# buckpuckV5_2014-12-10.net
KiCad netlist of a schematic drawn in EAGLE
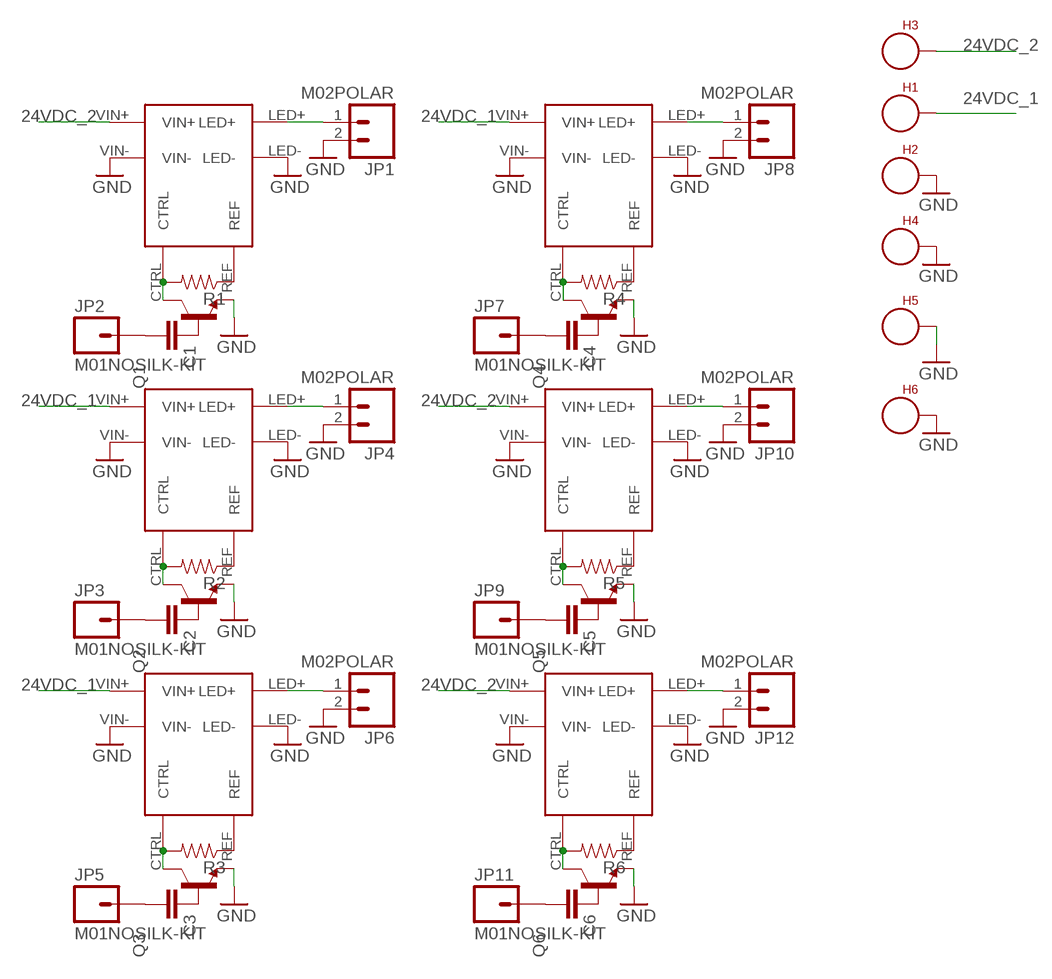
[diagram p0: schematic, sheet 1]

(export (version "E")
  (design (tool "Eeschema 10.0.6"))
  (components
    (comp (ref "C1")
      (value "CAPEZ")
      (footprint "eagle-import:CAP-PTH-SMALLEZ")
      (libsource (lib "eagle-import") (part "CAPEZ"))
    )
    (comp (ref "C2")
      (value "CAPEZ")
      (footprint "eagle-import:CAP-PTH-SMALLEZ")
      (libsource (lib "eagle-import") (part "CAPEZ"))
    )
    (comp (ref "C3")
      (value "CAPEZ")
      (footprint "eagle-import:CAP-PTH-SMALLEZ")
      (libsource (lib "eagle-import") (part "CAPEZ"))
    )
    (comp (ref "C4")
      (value "CAPEZ")
      (footprint "eagle-import:CAP-PTH-SMALLEZ")
      (libsource (lib "eagle-import") (part "CAPEZ"))
    )
    (comp (ref "C5")
      (value "CAPEZ")
      (footprint "eagle-import:CAP-PTH-SMALLEZ")
      (libsource (lib "eagle-import") (part "CAPEZ"))
    )
    (comp (ref "C6")
      (value "CAPEZ")
      (footprint "eagle-import:CAP-PTH-SMALLEZ")
      (libsource (lib "eagle-import") (part "CAPEZ"))
    )
    (comp (ref "H1")
      (value "SEW_HOLE")
      (footprint "eagle-import:SIMPLE_HOLE")
      (libsource (lib "eagle-import") (part "SEW_HOLE"))
    )
    (comp (ref "H2")
      (value "SEW_HOLE")
      (footprint "eagle-import:SIMPLE_HOLE")
      (libsource (lib "eagle-import") (part "SEW_HOLE"))
    )
    (comp (ref "H3")
      (value "SEW_HOLE")
      (footprint "eagle-import:SIMPLE_HOLE")
      (libsource (lib "eagle-import") (part "SEW_HOLE"))
    )
    (comp (ref "H4")
      (value "SEW_HOLE")
      (footprint "eagle-import:SIMPLE_HOLE")
      (libsource (lib "eagle-import") (part "SEW_HOLE"))
    )
    (comp (ref "H5")
      (value "SEW_HOLE")
      (footprint "eagle-import:SIMPLE_HOLE")
      (libsource (lib "eagle-import") (part "SEW_HOLE"))
    )
    (comp (ref "H6")
      (value "SEW_HOLE")
      (footprint "eagle-import:SIMPLE_HOLE")
      (libsource (lib "eagle-import") (part "SEW_HOLE"))
    )
    (comp (ref "JP1")
      (value "M02POLAR")
      (footprint "eagle-import:MOLEX-1X2")
      (libsource (lib "eagle-import") (part "M02POLAR"))
    )
    (comp (ref "JP2")
      (value "M01NOSILK-KIT")
      (footprint "eagle-import:1X01NS-KIT")
      (libsource (lib "eagle-import") (part "M01NOSILK-KIT"))
    )
    (comp (ref "JP3")
      (value "M01NOSILK-KIT")
      (footprint "eagle-import:1X01NS-KIT")
      (libsource (lib "eagle-import") (part "M01NOSILK-KIT"))
    )
    (comp (ref "JP4")
      (value "M02POLAR")
      (footprint "eagle-import:MOLEX-1X2")
      (libsource (lib "eagle-import") (part "M02POLAR"))
    )
    (comp (ref "JP5")
      (value "M01NOSILK-KIT")
      (footprint "eagle-import:1X01NS-KIT")
      (libsource (lib "eagle-import") (part "M01NOSILK-KIT"))
    )
    (comp (ref "JP6")
      (value "M02POLAR")
      (footprint "eagle-import:MOLEX-1X2")
      (libsource (lib "eagle-import") (part "M02POLAR"))
    )
    (comp (ref "JP7")
      (value "M01NOSILK-KIT")
      (footprint "eagle-import:1X01NS-KIT")
      (libsource (lib "eagle-import") (part "M01NOSILK-KIT"))
    )
    (comp (ref "JP8")
      (value "M02POLAR")
      (footprint "eagle-import:MOLEX-1X2")
      (libsource (lib "eagle-import") (part "M02POLAR"))
    )
    (comp (ref "JP9")
      (value "M01NOSILK-KIT")
      (footprint "eagle-import:1X01NS-KIT")
      (libsource (lib "eagle-import") (part "M01NOSILK-KIT"))
    )
    (comp (ref "JP10")
      (value "M02POLAR")
      (footprint "eagle-import:MOLEX-1X2")
      (libsource (lib "eagle-import") (part "M02POLAR"))
    )
    (comp (ref "JP11")
      (value "M01NOSILK-KIT")
      (footprint "eagle-import:1X01NS-KIT")
      (libsource (lib "eagle-import") (part "M01NOSILK-KIT"))
    )
    (comp (ref "JP12")
      (value "M02POLAR")
      (footprint "eagle-import:MOLEX-1X2")
      (libsource (lib "eagle-import") (part "M02POLAR"))
    )
    (comp (ref "Q1")
      (value "TRANSISTOR_BJT_NPN-TO-92-EBC")
      (footprint "eagle-import:TO-92")
      (libsource (lib "eagle-import") (part "TRANSISTOR_BJT_NPN-TO-92-EBC"))
    )
    (comp (ref "Q2")
      (value "TRANSISTOR_BJT_NPN-TO-92-EBC")
      (footprint "eagle-import:TO-92")
      (libsource (lib "eagle-import") (part "TRANSISTOR_BJT_NPN-TO-92-EBC"))
    )
    (comp (ref "Q3")
      (value "TRANSISTOR_BJT_NPN-TO-92-EBC")
      (footprint "eagle-import:TO-92")
      (libsource (lib "eagle-import") (part "TRANSISTOR_BJT_NPN-TO-92-EBC"))
    )
    (comp (ref "Q4")
      (value "TRANSISTOR_BJT_NPN-TO-92-EBC")
      (footprint "eagle-import:TO-92")
      (libsource (lib "eagle-import") (part "TRANSISTOR_BJT_NPN-TO-92-EBC"))
    )
    (comp (ref "Q5")
      (value "TRANSISTOR_BJT_NPN-TO-92-EBC")
      (footprint "eagle-import:TO-92")
      (libsource (lib "eagle-import") (part "TRANSISTOR_BJT_NPN-TO-92-EBC"))
    )
    (comp (ref "Q6")
      (value "TRANSISTOR_BJT_NPN-TO-92-EBC")
      (footprint "eagle-import:TO-92")
      (libsource (lib "eagle-import") (part "TRANSISTOR_BJT_NPN-TO-92-EBC"))
    )
    (comp (ref "R1")
      (value "RESISTOREZ")
      (footprint "eagle-import:AXIAL-0.3EZ")
      (libsource (lib "eagle-import") (part "RESISTOREZ"))
    )
    (comp (ref "R2")
      (value "RESISTOREZ")
      (footprint "eagle-import:AXIAL-0.3EZ")
      (libsource (lib "eagle-import") (part "RESISTOREZ"))
    )
    (comp (ref "R3")
      (value "RESISTOREZ")
      (footprint "eagle-import:AXIAL-0.3EZ")
      (libsource (lib "eagle-import") (part "RESISTOREZ"))
    )
    (comp (ref "R4")
      (value "RESISTOREZ")
      (footprint "eagle-import:AXIAL-0.3EZ")
      (libsource (lib "eagle-import") (part "RESISTOREZ"))
    )
    (comp (ref "R5")
      (value "RESISTOREZ")
      (footprint "eagle-import:AXIAL-0.3EZ")
      (libsource (lib "eagle-import") (part "RESISTOREZ"))
    )
    (comp (ref "R6")
      (value "RESISTOREZ")
      (footprint "eagle-import:AXIAL-0.3EZ")
      (libsource (lib "eagle-import") (part "RESISTOREZ"))
    )
    (comp (ref "U$1")
      (value "BUCKPUCK")
      (footprint "eagle-import:BUCKPUCK")
      (libsource (lib "eagle-import") (part "BUCKPUCK"))
    )
    (comp (ref "U$2")
      (value "BUCKPUCK")
      (footprint "eagle-import:BUCKPUCK")
      (libsource (lib "eagle-import") (part "BUCKPUCK"))
    )
    (comp (ref "U$3")
      (value "BUCKPUCK")
      (footprint "eagle-import:BUCKPUCK")
      (libsource (lib "eagle-import") (part "BUCKPUCK"))
    )
    (comp (ref "U$4")
      (value "BUCKPUCK")
      (footprint "eagle-import:BUCKPUCK")
      (libsource (lib "eagle-import") (part "BUCKPUCK"))
    )
    (comp (ref "U$5")
      (value "BUCKPUCK")
      (footprint "eagle-import:BUCKPUCK")
      (libsource (lib "eagle-import") (part "BUCKPUCK"))
    )
    (comp (ref "U$6")
      (value "BUCKPUCK")
      (footprint "eagle-import:BUCKPUCK")
      (libsource (lib "eagle-import") (part "BUCKPUCK"))
    )
  )
  (nets
    (net (code "1") (name "/24VDC_1") (class "Default")
      (node (ref "H1") (pin "P$1") (pinfunction "P$1_P$1") (pintype "bidirectional"))
      (node (ref "U$2") (pin "VIN+") (pinfunction "VIN+_VIN+") (pintype "bidirectional"))
      (node (ref "U$3") (pin "VIN+") (pinfunction "VIN+_VIN+") (pintype "bidirectional"))
      (node (ref "U$4") (pin "VIN+") (pinfunction "VIN+_VIN+") (pintype "bidirectional"))
    )
    (net (code "2") (name "/24VDC_2") (class "Default")
      (node (ref "H3") (pin "P$1") (pinfunction "P$1_P$1") (pintype "bidirectional"))
      (node (ref "U$1") (pin "VIN+") (pinfunction "VIN+_VIN+") (pintype "bidirectional"))
      (node (ref "U$5") (pin "VIN+") (pinfunction "VIN+_VIN+") (pintype "bidirectional"))
      (node (ref "U$6") (pin "VIN+") (pinfunction "VIN+_VIN+") (pintype "bidirectional"))
    )
    (net (code "3") (name "GND") (class "Default")
      (node (ref "H2") (pin "P$1") (pinfunction "P$1_P$1") (pintype "bidirectional"))
      (node (ref "H4") (pin "P$1") (pinfunction "P$1_P$1") (pintype "bidirectional"))
      (node (ref "H5") (pin "P$1") (pinfunction "P$1_P$1") (pintype "bidirectional"))
      (node (ref "H6") (pin "P$1") (pinfunction "P$1_P$1") (pintype "bidirectional"))
      (node (ref "JP1") (pin "2") (pinfunction "2_2") (pintype "passive"))
      (node (ref "JP10") (pin "2") (pinfunction "2_2") (pintype "passive"))
      (node (ref "JP12") (pin "2") (pinfunction "2_2") (pintype "passive"))
      (node (ref "JP4") (pin "2") (pinfunction "2_2") (pintype "passive"))
      (node (ref "JP6") (pin "2") (pinfunction "2_2") (pintype "passive"))
      (node (ref "JP8") (pin "2") (pinfunction "2_2") (pintype "passive"))
      (node (ref "Q1") (pin "1") (pinfunction "E_1") (pintype "passive"))
      (node (ref "Q2") (pin "1") (pinfunction "E_1") (pintype "passive"))
      (node (ref "Q3") (pin "1") (pinfunction "E_1") (pintype "passive"))
      (node (ref "Q4") (pin "1") (pinfunction "E_1") (pintype "passive"))
      (node (ref "Q5") (pin "1") (pinfunction "E_1") (pintype "passive"))
      (node (ref "Q6") (pin "1") (pinfunction "E_1") (pintype "passive"))
      (node (ref "U$1") (pin "LED-") (pinfunction "LED-_LED-") (pintype "bidirectional"))
      (node (ref "U$1") (pin "VIN-") (pinfunction "VIN-_VIN-") (pintype "bidirectional"))
      (node (ref "U$2") (pin "LED-") (pinfunction "LED-_LED-") (pintype "bidirectional"))
      (node (ref "U$2") (pin "VIN-") (pinfunction "VIN-_VIN-") (pintype "bidirectional"))
      (node (ref "U$3") (pin "LED-") (pinfunction "LED-_LED-") (pintype "bidirectional"))
      (node (ref "U$3") (pin "VIN-") (pinfunction "VIN-_VIN-") (pintype "bidirectional"))
      (node (ref "U$4") (pin "LED-") (pinfunction "LED-_LED-") (pintype "bidirectional"))
      (node (ref "U$4") (pin "VIN-") (pinfunction "VIN-_VIN-") (pintype "bidirectional"))
      (node (ref "U$5") (pin "LED-") (pinfunction "LED-_LED-") (pintype "bidirectional"))
      (node (ref "U$5") (pin "VIN-") (pinfunction "VIN-_VIN-") (pintype "bidirectional"))
      (node (ref "U$6") (pin "LED-") (pinfunction "LED-_LED-") (pintype "bidirectional"))
      (node (ref "U$6") (pin "VIN-") (pinfunction "VIN-_VIN-") (pintype "bidirectional"))
    )
    (net (code "4") (name "Net-(C1-Pad2)") (class "Default")
      (node (ref "C1") (pin "2") (pinfunction "2_2") (pintype "passive"))
      (node (ref "JP2") (pin "1") (pinfunction "1_1") (pintype "passive"))
    )
    (net (code "5") (name "Net-(C2-Pad2)") (class "Default")
      (node (ref "C2") (pin "2") (pinfunction "2_2") (pintype "passive"))
      (node (ref "JP3") (pin "1") (pinfunction "1_1") (pintype "passive"))
    )
    (net (code "6") (name "Net-(C3-Pad2)") (class "Default")
      (node (ref "C3") (pin "2") (pinfunction "2_2") (pintype "passive"))
      (node (ref "JP5") (pin "1") (pinfunction "1_1") (pintype "passive"))
    )
    (net (code "7") (name "Net-(C4-Pad2)") (class "Default")
      (node (ref "C4") (pin "2") (pinfunction "2_2") (pintype "passive"))
      (node (ref "JP7") (pin "1") (pinfunction "1_1") (pintype "passive"))
    )
    (net (code "8") (name "Net-(C5-Pad2)") (class "Default")
      (node (ref "C5") (pin "2") (pinfunction "2_2") (pintype "passive"))
      (node (ref "JP9") (pin "1") (pinfunction "1_1") (pintype "passive"))
    )
    (net (code "9") (name "Net-(C6-Pad2)") (class "Default")
      (node (ref "C6") (pin "2") (pinfunction "2_2") (pintype "passive"))
      (node (ref "JP11") (pin "1") (pinfunction "1_1") (pintype "passive"))
    )
    (net (code "10") (name "Net-(JP1-Pad1)") (class "Default")
      (node (ref "JP1") (pin "1") (pinfunction "1_1") (pintype "passive"))
      (node (ref "U$1") (pin "LED+") (pinfunction "LED+_LED+") (pintype "bidirectional"))
    )
    (net (code "11") (name "Net-(JP4-Pad1)") (class "Default")
      (node (ref "JP4") (pin "1") (pinfunction "1_1") (pintype "passive"))
      (node (ref "U$2") (pin "LED+") (pinfunction "LED+_LED+") (pintype "bidirectional"))
    )
    (net (code "12") (name "Net-(JP6-Pad1)") (class "Default")
      (node (ref "JP6") (pin "1") (pinfunction "1_1") (pintype "passive"))
      (node (ref "U$3") (pin "LED+") (pinfunction "LED+_LED+") (pintype "bidirectional"))
    )
    (net (code "13") (name "Net-(JP8-Pad1)") (class "Default")
      (node (ref "JP8") (pin "1") (pinfunction "1_1") (pintype "passive"))
      (node (ref "U$4") (pin "LED+") (pinfunction "LED+_LED+") (pintype "bidirectional"))
    )
    (net (code "14") (name "Net-(JP10-Pad1)") (class "Default")
      (node (ref "JP10") (pin "1") (pinfunction "1_1") (pintype "passive"))
      (node (ref "U$5") (pin "LED+") (pinfunction "LED+_LED+") (pintype "bidirectional"))
    )
    (net (code "15") (name "Net-(JP12-Pad1)") (class "Default")
      (node (ref "JP12") (pin "1") (pinfunction "1_1") (pintype "passive"))
      (node (ref "U$6") (pin "LED+") (pinfunction "LED+_LED+") (pintype "bidirectional"))
    )
    (net (code "16") (name "Net-(Q1-B)") (class "Default")
      (node (ref "C1") (pin "1") (pinfunction "1_1") (pintype "passive"))
      (node (ref "Q1") (pin "2") (pinfunction "B_2") (pintype "passive"))
    )
    (net (code "17") (name "Net-(Q1-C)") (class "Default")
      (node (ref "Q1") (pin "3") (pinfunction "C_3") (pintype "passive"))
      (node (ref "R1") (pin "P$2") (pinfunction "2_P$2") (pintype "passive"))
      (node (ref "U$1") (pin "CTRL") (pinfunction "CTRL_CTRL") (pintype "bidirectional"))
    )
    (net (code "18") (name "Net-(Q2-B)") (class "Default")
      (node (ref "C2") (pin "1") (pinfunction "1_1") (pintype "passive"))
      (node (ref "Q2") (pin "2") (pinfunction "B_2") (pintype "passive"))
    )
    (net (code "19") (name "Net-(Q2-C)") (class "Default")
      (node (ref "Q2") (pin "3") (pinfunction "C_3") (pintype "passive"))
      (node (ref "R2") (pin "P$2") (pinfunction "2_P$2") (pintype "passive"))
      (node (ref "U$2") (pin "CTRL") (pinfunction "CTRL_CTRL") (pintype "bidirectional"))
    )
    (net (code "20") (name "Net-(Q3-B)") (class "Default")
      (node (ref "C3") (pin "1") (pinfunction "1_1") (pintype "passive"))
      (node (ref "Q3") (pin "2") (pinfunction "B_2") (pintype "passive"))
    )
    (net (code "21") (name "Net-(Q3-C)") (class "Default")
      (node (ref "Q3") (pin "3") (pinfunction "C_3") (pintype "passive"))
      (node (ref "R3") (pin "P$2") (pinfunction "2_P$2") (pintype "passive"))
      (node (ref "U$3") (pin "CTRL") (pinfunction "CTRL_CTRL") (pintype "bidirectional"))
    )
    (net (code "22") (name "Net-(Q4-B)") (class "Default")
      (node (ref "C4") (pin "1") (pinfunction "1_1") (pintype "passive"))
      (node (ref "Q4") (pin "2") (pinfunction "B_2") (pintype "passive"))
    )
    (net (code "23") (name "Net-(Q4-C)") (class "Default")
      (node (ref "Q4") (pin "3") (pinfunction "C_3") (pintype "passive"))
      (node (ref "R4") (pin "P$2") (pinfunction "2_P$2") (pintype "passive"))
      (node (ref "U$4") (pin "CTRL") (pinfunction "CTRL_CTRL") (pintype "bidirectional"))
    )
    (net (code "24") (name "Net-(Q5-B)") (class "Default")
      (node (ref "C5") (pin "1") (pinfunction "1_1") (pintype "passive"))
      (node (ref "Q5") (pin "2") (pinfunction "B_2") (pintype "passive"))
    )
    (net (code "25") (name "Net-(Q5-C)") (class "Default")
      (node (ref "Q5") (pin "3") (pinfunction "C_3") (pintype "passive"))
      (node (ref "R5") (pin "P$2") (pinfunction "2_P$2") (pintype "passive"))
      (node (ref "U$5") (pin "CTRL") (pinfunction "CTRL_CTRL") (pintype "bidirectional"))
    )
    (net (code "26") (name "Net-(Q6-B)") (class "Default")
      (node (ref "C6") (pin "1") (pinfunction "1_1") (pintype "passive"))
      (node (ref "Q6") (pin "2") (pinfunction "B_2") (pintype "passive"))
    )
    (net (code "27") (name "Net-(Q6-C)") (class "Default")
      (node (ref "Q6") (pin "3") (pinfunction "C_3") (pintype "passive"))
      (node (ref "R6") (pin "P$2") (pinfunction "2_P$2") (pintype "passive"))
      (node (ref "U$6") (pin "CTRL") (pinfunction "CTRL_CTRL") (pintype "bidirectional"))
    )
    (net (code "28") (name "Net-(R1-1)") (class "Default")
      (node (ref "R1") (pin "P$1") (pinfunction "1_P$1") (pintype "passive"))
      (node (ref "U$1") (pin "REF") (pinfunction "REF_REF") (pintype "bidirectional"))
    )
    (net (code "29") (name "Net-(R2-1)") (class "Default")
      (node (ref "R2") (pin "P$1") (pinfunction "1_P$1") (pintype "passive"))
      (node (ref "U$2") (pin "REF") (pinfunction "REF_REF") (pintype "bidirectional"))
    )
    (net (code "30") (name "Net-(R3-1)") (class "Default")
      (node (ref "R3") (pin "P$1") (pinfunction "1_P$1") (pintype "passive"))
      (node (ref "U$3") (pin "REF") (pinfunction "REF_REF") (pintype "bidirectional"))
    )
    (net (code "31") (name "Net-(R4-1)") (class "Default")
      (node (ref "R4") (pin "P$1") (pinfunction "1_P$1") (pintype "passive"))
      (node (ref "U$4") (pin "REF") (pinfunction "REF_REF") (pintype "bidirectional"))
    )
    (net (code "32") (name "Net-(R5-1)") (class "Default")
      (node (ref "R5") (pin "P$1") (pinfunction "1_P$1") (pintype "passive"))
      (node (ref "U$5") (pin "REF") (pinfunction "REF_REF") (pintype "bidirectional"))
    )
    (net (code "33") (name "Net-(R6-1)") (class "Default")
      (node (ref "R6") (pin "P$1") (pinfunction "1_P$1") (pintype "passive"))
      (node (ref "U$6") (pin "REF") (pinfunction "REF_REF") (pintype "bidirectional"))
    )
  )
)
